# Sheet1.net
KiCad netlist of a schematic drawn in Altium Designer
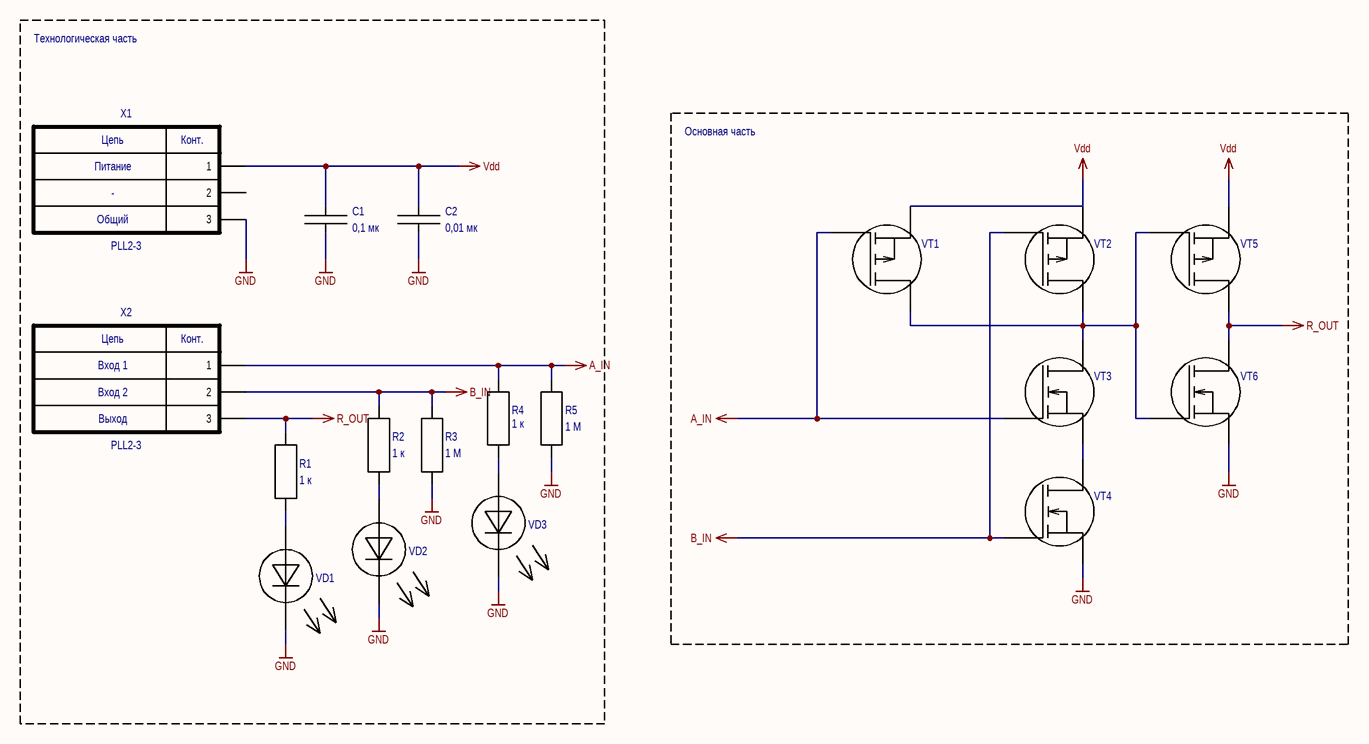
[diagram p0: Sheet1.SchDoc]

(export (version "E")
  (design (tool "Eeschema 10.0.6"))
  (components
    (comp (ref "C1")
      (value "0,1 мк")
      (footprint "K10-79_1.6_0.8(0603)")
      (fields
        (field (name "PARTNUMBER") "CC0603JRX7R8BB104")
        (field (name "TOLERANCE") "5 %")
        (field (name "Comment") "0,1 мкФ ±5 % *  0603, CC0603JRX7R8BB104")
      )
      (libsource (lib "ALU") (part "C - Конденсатор"))
    )
    (comp (ref "C2")
      (value "0,01 мк")
      (footprint "K10-79_1.6_0.8(0603)")
      (fields
        (field (name "PARTNUMBER") "CC0603KPX7R8BB103")
        (field (name "TOLERANCE") "10 %")
        (field (name "Comment") "0,01 мкФ ±10 % *  0603, CC0603KPX7R8BB103")
      )
      (libsource (lib "ALU") (part "C - Конденсатор"))
    )
    (comp (ref "R1")
      (value "1 к")
      (footprint "ALU:P1-12-0.1(0603)")
      (fields
        (field (name "PARTNUMBER") "RC0603JR-071KL")
        (field (name "TOLERANCE") "5 %")
        (field (name "Comment") "1 кОм ±5 % 0603, RC0603JR-071KL")
      )
      (libsource (lib "ALU") (part "R - Резистор"))
    )
    (comp (ref "R2")
      (value "1 к")
      (footprint "ALU:P1-12-0.1(0603)")
      (fields
        (field (name "PARTNUMBER") "RC0603JR-071KL")
        (field (name "TOLERANCE") "5 %")
        (field (name "Comment") "1 кОм ±5 % 0603, RC0603JR-071KL")
      )
      (libsource (lib "ALU") (part "R - Резистор"))
    )
    (comp (ref "R3")
      (value "1 М")
      (footprint "ALU:P1-12-0.1(0603)")
      (fields
        (field (name "PARTNUMBER") "RC0603JR-071KL")
        (field (name "TOLERANCE") "5 %")
        (field (name "Comment") "1 кОм ±5 % 0603, RC0603JR-071KL")
      )
      (libsource (lib "ALU") (part "R - Резистор"))
    )
    (comp (ref "R4")
      (value "1 к")
      (footprint "ALU:P1-12-0.1(0603)")
      (fields
        (field (name "PARTNUMBER") "RC0603JR-071KL")
        (field (name "TOLERANCE") "5 %")
        (field (name "Comment") "1 кОм ±5 % 0603, RC0603JR-071KL")
      )
      (libsource (lib "ALU") (part "R - Резистор"))
    )
    (comp (ref "R5")
      (value "1 М")
      (footprint "ALU:P1-12-0.1(0603)")
      (fields
        (field (name "PARTNUMBER") "RC0603JR-071KL")
        (field (name "TOLERANCE") "5 %")
        (field (name "Comment") "1 кОм ±5 % 0603, RC0603JR-071KL")
      )
      (libsource (lib "ALU") (part "R - Резистор"))
    )
    (comp (ref "VD1")
      (value "VD - Светодиод")
      (footprint "LED 0603")
      (fields (field (name "PARTNUMBER") "GNL-0805UBC-TL"))
      (libsource (lib "ALU") (part "VD - Светодиод"))
    )
    (comp (ref "VD2")
      (value "VD - Светодиод")
      (footprint "LED 0603")
      (fields (field (name "PARTNUMBER") "GNL-0805UBC-TL"))
      (libsource (lib "ALU") (part "VD - Светодиод"))
    )
    (comp (ref "VD3")
      (value "VD - Светодиод")
      (footprint "LED 0603")
      (fields (field (name "PARTNUMBER") "GNL-0805UBC-TL"))
      (libsource (lib "ALU") (part "VD - Светодиод"))
    )
    (comp (ref "VT1")
      (value "VT - Полевой транзистор P канал (MOSFET_P)")
      (footprint "SOT23(KT-46)")
      (description "VT")
      (libsource (lib "ALU") (part "VT - Полевой транзистор P канал (MOSFET_P)"))
    )
    (comp (ref "VT2")
      (value "VT - Полевой транзистор P канал (MOSFET_P)")
      (footprint "SOT23(KT-46)")
      (description "VT")
      (libsource (lib "ALU") (part "VT - Полевой транзистор P канал (MOSFET_P)"))
    )
    (comp (ref "VT3")
      (value "VT - Полевой транзистор N канал (MOSFET_N)")
      (footprint "SOT23(KT-46)")
      (description "VT")
      (libsource (lib "ALU") (part "VT - Полевой транзистор N канал (MOSFET_N)"))
    )
    (comp (ref "VT4")
      (value "VT - Полевой транзистор N канал (MOSFET_N)")
      (footprint "SOT23(KT-46)")
      (description "VT")
      (libsource (lib "ALU") (part "VT - Полевой транзистор N канал (MOSFET_N)"))
    )
    (comp (ref "VT5")
      (value "VT - Полевой транзистор P канал (MOSFET_P)")
      (footprint "SOT23(KT-46)")
      (description "VT")
      (libsource (lib "ALU") (part "VT - Полевой транзистор P канал (MOSFET_P)"))
    )
    (comp (ref "VT6")
      (value "VT - Полевой транзистор N канал (MOSFET_N)")
      (footprint "SOT23(KT-46)")
      (description "VT")
      (libsource (lib "ALU") (part "VT - Полевой транзистор N канал (MOSFET_N)"))
    )
    (comp (ref "X1")
      (value "PLL2-3")
      (footprint "AND:PCBComponent_1 - duplicate")
      (fields
        (field (name "1") "Питание")
        (field (name "3") "Общий")
        (field (name "2") "-")
        (field (name "Comment") "KONT_POLE_POWER")
      )
      (libsource (lib "components") (part "X - Контактное поле х3"))
    )
    (comp (ref "X2")
      (value "PLL2-3")
      (footprint "AND:PCBComponent_1 - duplicate")
      (fields
        (field (name "1") "Вход 1")
        (field (name "3") "Выход")
        (field (name "2") "Вход 2")
        (field (name "Comment") "KONT_POLE_POWER")
      )
      (libsource (lib "components") (part "X - Контактное поле х3"))
    )
  )
  (nets
    (net (code "1") (name "A_IN") (class "Default")
      (node (ref "R4") (pin "2") (pinfunction "2_2") (pintype "passive"))
      (node (ref "R5") (pin "2") (pinfunction "2_2") (pintype "passive"))
      (node (ref "VT1") (pin "3") (pintype "passive"))
      (node (ref "VT3") (pin "3") (pintype "passive"))
      (node (ref "X2") (pin "1") (pinfunction "1_1") (pintype "passive"))
    )
    (net (code "2") (name "B_IN") (class "Default")
      (node (ref "R2") (pin "2") (pinfunction "2_2") (pintype "passive"))
      (node (ref "R3") (pin "2") (pinfunction "2_2") (pintype "passive"))
      (node (ref "VT2") (pin "3") (pintype "passive"))
      (node (ref "VT4") (pin "3") (pintype "passive"))
      (node (ref "X2") (pin "2") (pinfunction "2_2") (pintype "passive"))
    )
    (net (code "3") (name "GND") (class "Default")
      (node (ref "C1") (pin "1") (pinfunction "1_1") (pintype "passive"))
      (node (ref "C2") (pin "1") (pinfunction "1_1") (pintype "passive"))
      (node (ref "R3") (pin "1") (pinfunction "1_1") (pintype "passive"))
      (node (ref "R5") (pin "1") (pinfunction "1_1") (pintype "passive"))
      (node (ref "VD1") (pin "2") (pinfunction "C_2") (pintype "passive"))
      (node (ref "VD2") (pin "2") (pinfunction "C_2") (pintype "passive"))
      (node (ref "VD3") (pin "2") (pinfunction "C_2") (pintype "passive"))
      (node (ref "VT4") (pin "2") (pintype "passive"))
      (node (ref "VT6") (pin "2") (pintype "passive"))
      (node (ref "X1") (pin "3") (pinfunction "3_3") (pintype "passive"))
    )
    (net (code "4") (name "Net-(VD1-A)") (class "Default")
      (node (ref "R1") (pin "1") (pinfunction "1_1") (pintype "passive"))
      (node (ref "VD1") (pin "1") (pinfunction "A_1") (pintype "passive"))
    )
    (net (code "5") (name "Net-(VD2-A)") (class "Default")
      (node (ref "R2") (pin "1") (pinfunction "1_1") (pintype "passive"))
      (node (ref "VD2") (pin "1") (pinfunction "A_1") (pintype "passive"))
    )
    (net (code "6") (name "Net-(VD3-A)") (class "Default")
      (node (ref "R4") (pin "1") (pinfunction "1_1") (pintype "passive"))
      (node (ref "VD3") (pin "1") (pinfunction "A_1") (pintype "passive"))
    )
    (net (code "7") (name "Net-(VT1-Pad2)") (class "Default")
      (node (ref "VT1") (pin "2") (pintype "passive"))
      (node (ref "VT2") (pin "2") (pintype "passive"))
      (node (ref "VT3") (pin "1") (pintype "passive"))
      (node (ref "VT5") (pin "3") (pintype "passive"))
      (node (ref "VT6") (pin "3") (pintype "passive"))
    )
    (net (code "8") (name "Net-(VT3-Pad2)") (class "Default")
      (node (ref "VT3") (pin "2") (pintype "passive"))
      (node (ref "VT4") (pin "1") (pintype "passive"))
    )
    (net (code "9") (name "R_OUT") (class "Default")
      (node (ref "R1") (pin "2") (pinfunction "2_2") (pintype "passive"))
      (node (ref "VT5") (pin "2") (pintype "passive"))
      (node (ref "VT6") (pin "1") (pintype "passive"))
      (node (ref "X2") (pin "3") (pinfunction "3_3") (pintype "passive"))
    )
    (net (code "10") (name "Vdd") (class "Default")
      (node (ref "C1") (pin "2") (pinfunction "2_2") (pintype "passive"))
      (node (ref "C2") (pin "2") (pinfunction "2_2") (pintype "passive"))
      (node (ref "VT1") (pin "1") (pintype "passive"))
      (node (ref "VT2") (pin "1") (pintype "passive"))
      (node (ref "VT5") (pin "1") (pintype "passive"))
      (node (ref "X1") (pin "1") (pinfunction "1_1") (pintype "passive"))
    )
    (net (code "11") (name "unconnected-(X1-Pad2)") (class "Default")
      (node (ref "X1") (pin "2") (pinfunction "2_2") (pintype "passive"))
    )
  )
)
